# TSL2561_Luminosity_Sensor_BOB.net
KiCad netlist of a schematic drawn in EAGLE
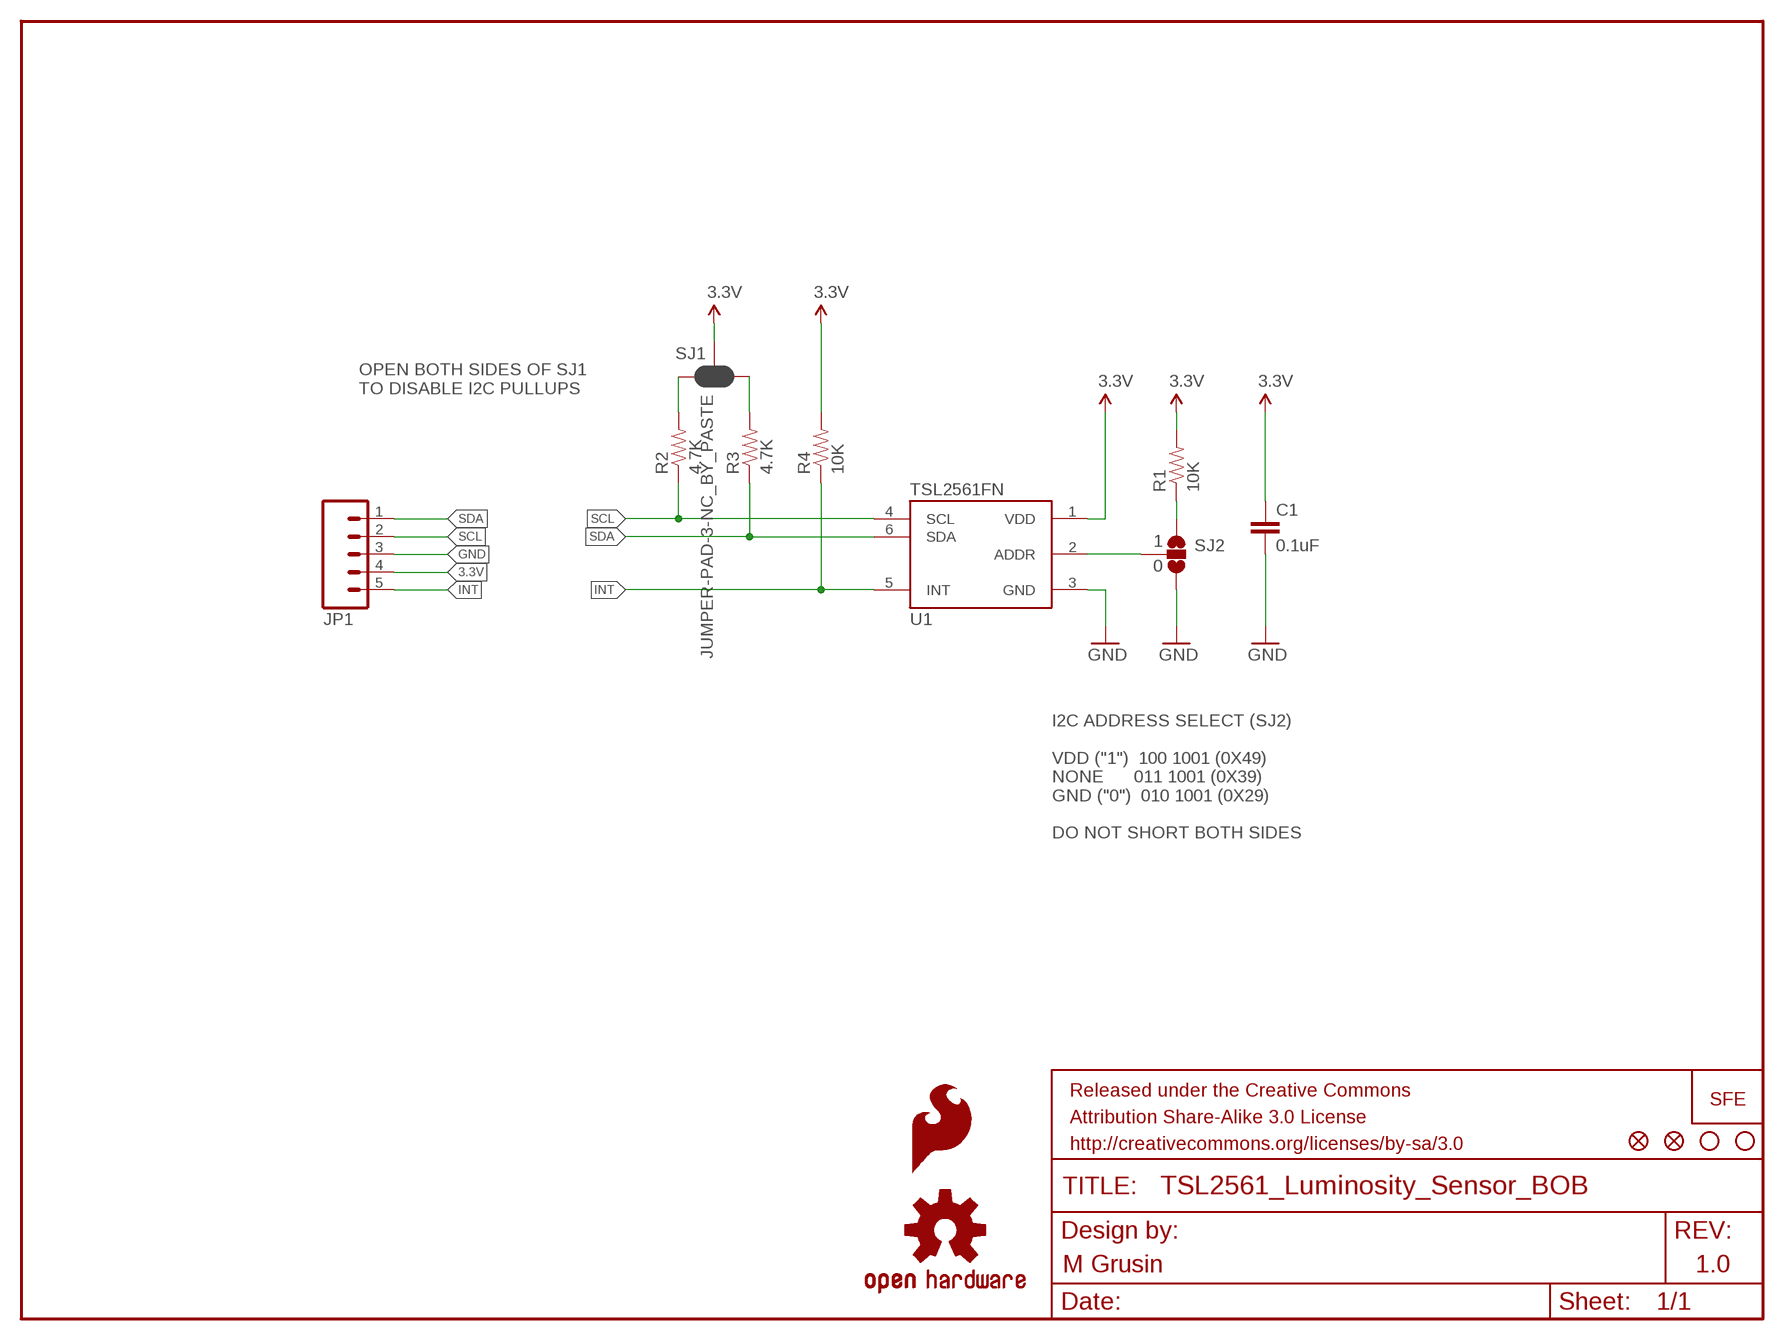
[diagram p0: schematic, sheet 1]

(export (version "E")
  (design (tool "Eeschema 10.0.6"))
  (components
    (comp (ref "C1")
      (value "0.1uF")
      (footprint "eagle-import:0603-CAP")
      (libsource (lib "eagle-import") (part "0.1UF-25V(+80/-20%)(0603)"))
    )
    (comp (ref "FID1")
      (value "FIDUCIALUFIDUCIAL")
      (footprint "eagle-import:MICRO-FIDUCIAL")
      (libsource (lib "eagle-import") (part "FIDUCIALUFIDUCIAL"))
    )
    (comp (ref "FID2")
      (value "FIDUCIALUFIDUCIAL")
      (footprint "eagle-import:MICRO-FIDUCIAL")
      (libsource (lib "eagle-import") (part "FIDUCIALUFIDUCIAL"))
    )
    (comp (ref "FRAME1")
      (value "FRAME-LETTER")
      (footprint "eagle-import:CREATIVE_COMMONS")
      (libsource (lib "eagle-import") (part "FRAME-LETTER"))
    )
    (comp (ref "JP1")
      (value "M05NO_SILK")
      (footprint "eagle-import:1X05_NO_SILK")
      (libsource (lib "eagle-import") (part "M05NO_SILK"))
    )
    (comp (ref "LOGO1")
      (value "OSHW-LOGOS")
      (footprint "eagle-import:OSHW-LOGO-S")
      (libsource (lib "eagle-import") (part "OSHW-LOGOS"))
    )
    (comp (ref "LOGO2")
      (value "LOGO-SFENW2")
      (footprint "eagle-import:SFE-NEW-WEB")
      (libsource (lib "eagle-import") (part "LOGO-SFENW2"))
    )
    (comp (ref "LOGO3")
      (value "SFE_LOGO_FLAME.1_INCH")
      (footprint "eagle-import:SFE_LOGO_FLAME_.1")
      (libsource (lib "eagle-import") (part "SFE_LOGO_FLAME.1_INCH"))
    )
    (comp (ref "R1")
      (value "10K")
      (footprint "eagle-import:0603-RES")
      (libsource (lib "eagle-import") (part "10KOHM-1/10W-1%(0603)0603"))
    )
    (comp (ref "R2")
      (value "4.7K")
      (footprint "eagle-import:0603-RES")
      (libsource (lib "eagle-import") (part "4.7KOHM-1/10W-1%(0603)"))
    )
    (comp (ref "R3")
      (value "4.7K")
      (footprint "eagle-import:0603-RES")
      (libsource (lib "eagle-import") (part "4.7KOHM-1/10W-1%(0603)"))
    )
    (comp (ref "R4")
      (value "10K")
      (footprint "eagle-import:0603-RES")
      (libsource (lib "eagle-import") (part "10KOHM-1/10W-1%(0603)0603"))
    )
    (comp (ref "SJ1")
      (value "JUMPER-PAD-3-NC_BY_PASTE")
      (footprint "eagle-import:PAD-JUMPER-3-NC_BY_PASTE_YES_SILK_FULL_BOX")
      (libsource (lib "eagle-import") (part "JUMPER-PAD-3-NC_BY_PASTE"))
    )
    (comp (ref "SJ2")
      (value "SOLDERJUMPER_2WAYS")
      (footprint "eagle-import:SJ_3")
      (libsource (lib "eagle-import") (part "SOLDERJUMPER_2WAYS"))
    )
    (comp (ref "STANDOFF1")
      (value "STAND-OFF")
      (footprint "eagle-import:STAND-OFF")
      (libsource (lib "eagle-import") (part "STAND-OFF"))
    )
    (comp (ref "STANDOFF2")
      (value "STAND-OFF")
      (footprint "eagle-import:STAND-OFF")
      (libsource (lib "eagle-import") (part "STAND-OFF"))
    )
    (comp (ref "U1")
      (value "TSL2561FN")
      (footprint "eagle-import:FN-6")
      (libsource (lib "eagle-import") (part "TSL2561FN"))
    )
  )
  (nets
    (net (code "1") (name "3.3V") (class "Default")
      (node (ref "C1") (pin "1") (pinfunction "1_1") (pintype "passive"))
      (node (ref "JP1") (pin "4") (pinfunction "4_4") (pintype "passive"))
      (node (ref "R1") (pin "2") (pinfunction "2_2") (pintype "passive"))
      (node (ref "R4") (pin "2") (pinfunction "2_2") (pintype "passive"))
      (node (ref "SJ1") (pin "2") (pinfunction "2_2") (pintype "passive"))
      (node (ref "U1") (pin "1") (pinfunction "VDD_1") (pintype "power_in"))
    )
    (net (code "2") (name "GND") (class "Default")
      (node (ref "C1") (pin "2") (pinfunction "2_2") (pintype "passive"))
      (node (ref "JP1") (pin "3") (pinfunction "3_3") (pintype "passive"))
      (node (ref "SJ2") (pin "3") (pinfunction "3_3") (pintype "passive"))
      (node (ref "U1") (pin "3") (pinfunction "GND_3") (pintype "power_in"))
    )
    (net (code "3") (name "INT") (class "Default")
      (node (ref "JP1") (pin "5") (pinfunction "5_5") (pintype "passive"))
      (node (ref "R4") (pin "1") (pinfunction "1_1") (pintype "passive"))
      (node (ref "U1") (pin "5") (pinfunction "INT_5") (pintype "output"))
    )
    (net (code "4") (name "Net-(R1-Pad1)") (class "Default")
      (node (ref "R1") (pin "1") (pinfunction "1_1") (pintype "passive"))
      (node (ref "SJ2") (pin "1") (pinfunction "1_1") (pintype "passive"))
    )
    (net (code "5") (name "Net-(R2-Pad2)") (class "Default")
      (node (ref "R2") (pin "2") (pinfunction "2_2") (pintype "passive"))
      (node (ref "SJ1") (pin "3") (pinfunction "3_3") (pintype "passive"))
    )
    (net (code "6") (name "Net-(R3-Pad2)") (class "Default")
      (node (ref "R3") (pin "2") (pinfunction "2_2") (pintype "passive"))
      (node (ref "SJ1") (pin "1") (pinfunction "1_1") (pintype "passive"))
    )
    (net (code "7") (name "Net-(U1-ADDR)") (class "Default")
      (node (ref "SJ2") (pin "2") (pinfunction "2_2") (pintype "passive"))
      (node (ref "U1") (pin "2") (pinfunction "ADDR_2") (pintype "input"))
    )
    (net (code "8") (name "SCL") (class "Default")
      (node (ref "JP1") (pin "2") (pinfunction "2_2") (pintype "passive"))
      (node (ref "R2") (pin "1") (pinfunction "1_1") (pintype "passive"))
      (node (ref "U1") (pin "4") (pinfunction "SCL_4") (pintype "input"))
    )
    (net (code "9") (name "SDA") (class "Default")
      (node (ref "JP1") (pin "1") (pinfunction "1_1") (pintype "passive"))
      (node (ref "R3") (pin "1") (pinfunction "1_1") (pintype "passive"))
      (node (ref "U1") (pin "6") (pinfunction "SDA_6") (pintype "bidirectional"))
    )
  )
)
